# 05_GAP_MIC.net
KiCad netlist of a schematic drawn in Altium Designer
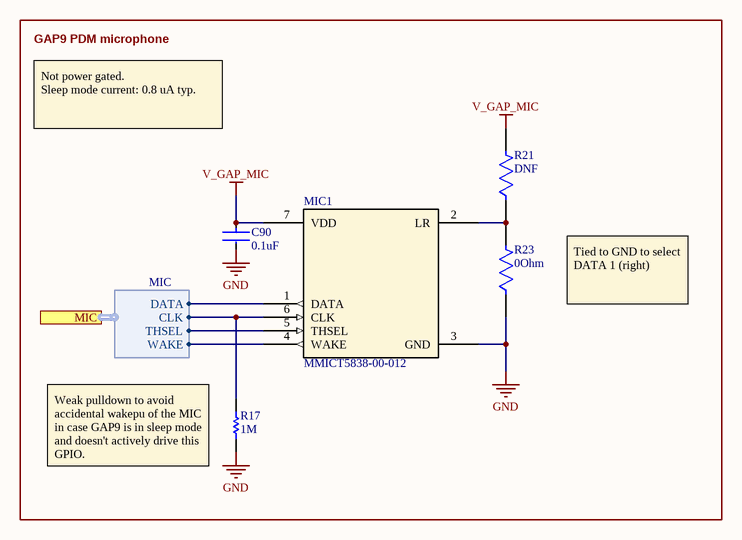
[diagram p0: 05_GAP_MIC.SchDoc]

(export (version "E")
  (design (tool "Eeschema 10.0.6"))
  (components
    (comp (ref "C90")
      (value "GRM033Z71C104KE14D")
      (footprint "FP-GRM033-0_03-IPC_B")
      (description "Chip Multilayer Ceramic Capacitors for General Purpose, 0201, 0.10uF, X7R, 15%, 10%, 16V")
      (fields (field (name "CAPACITANCE") "0.1uF"))
      (libsource (lib "Altium Content Vault") (part "b4654b650e69147ec39a6b967a45e02"))
    )
    (comp (ref "MIC1")
      (value "MMICT5838-00-012")
      (footprint "EEG_PcbLib:MMICT5838-00-012")
      (description "No Description Available")
      (fields (field (name "COPYRIGHT") "Copyright (C) 2023 Ultra Librarian. All rights reserved."))
      (libsource (lib "EEG_SchLib") (part "MMICT5838-00-012"))
    )
    (comp (ref "R17")
      (value "1M")
      (footprint "RESC0201(0603)_L")
      (description "1M 0.05W 5% 0201 (0603 Metric)  SMD")
      (fields (field (name "TOLERANCE") "5 %") (field (name "POWER") "0.05 W"))
      (libsource (lib "Altium Content Vault") (part "RES"))
    )
    (comp (ref "R21")
      (value "DNF")
      (footprint "FP-RMCF0201-IPC_C")
      (libsource (lib "Altium Content Vault") (part "1029c3af85768c4190bb7ad29bc67b5"))
    )
    (comp (ref "R23")
      (value "RMCF0201ZT0R00")
      (footprint "FP-RMCF0201-IPC_C")
      (description "0Ω ±0 0.05W 0201 Thick Film Chip Resistor AEC-Q200 compliant")
      (fields (field (name "RESISTANCE") "0Ohm"))
      (libsource (lib "Altium Content Vault") (part "1029c3af85768c4190bb7ad29bc67b5"))
    )
  )
  (nets
    (net (code "2") (name "/CLK") (class "Default")
      (node (ref "MIC1") (pin "6") (pinfunction "CLK_6") (pintype "input"))
      (node (ref "R17") (pin "2") (pinfunction "2_2") (pintype "passive"))
    )
    (net (code "3") (name "/DATA") (class "Default")
      (node (ref "MIC1") (pin "1") (pinfunction "DATA_1") (pintype "output"))
    )
    (net (code "4") (name "/THSEL") (class "Default")
      (node (ref "MIC1") (pin "5") (pinfunction "THSEL_5") (pintype "input"))
    )
    (net (code "5") (name "/WAKE") (class "Default")
      (node (ref "MIC1") (pin "4") (pinfunction "WAKE_4") (pintype "output"))
    )
    (net (code "7") (name "GND") (class "Default")
      (node (ref "C90") (pin "2") (pinfunction "2_2") (pintype "passive"))
      (node (ref "MIC1") (pin "3") (pinfunction "GND_3") (pintype "power_in"))
      (node (ref "R17") (pin "1") (pinfunction "1_1") (pintype "passive"))
      (node (ref "R23") (pin "1") (pinfunction "1_1") (pintype "passive"))
    )
    (net (code "8") (name "Net-(MIC1-LR)") (class "Default")
      (node (ref "MIC1") (pin "2") (pinfunction "LR_2") (pintype "passive"))
      (node (ref "R21") (pin "1") (pinfunction "1_1") (pintype "passive"))
      (node (ref "R23") (pin "2") (pinfunction "2_2") (pintype "passive"))
    )
    (net (code "9") (name "V_GAP_MIC") (class "Default")
      (node (ref "C90") (pin "1") (pinfunction "1_1") (pintype "passive"))
      (node (ref "MIC1") (pin "7") (pinfunction "VDD_7") (pintype "power_in"))
      (node (ref "R21") (pin "2") (pinfunction "2_2") (pintype "passive"))
    )
  )
)
